# Lab2-th.net
KiCad netlist of a schematic drawn in EAGLE
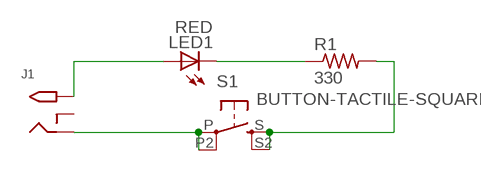
[diagram p0: schematic, sheet 1]

(export (version "E")
  (design (tool "Eeschema 10.0.6"))
  (components
    (comp (ref "J1")
      (value "2.1MMJACKTHM")
      (footprint "eagle-import:PJ-102A")
      (libsource (lib "eagle-import") (part "2.1MMJACKTHM"))
    )
    (comp (ref "LED1")
      (value "RED")
      (footprint "eagle-import:LED5MM")
      (libsource (lib "eagle-import") (part "LED5MM"))
    )
    (comp (ref "R1")
      (value "330")
      (footprint "eagle-import:RESAD1160W55L680D260_HS")
      (libsource (lib "eagle-import") (part "RESISTORTH-1/4W-CARBON"))
    )
    (comp (ref "S1")
      (value "BUTTON-TACTILE-SQUARE")
      (footprint "eagle-import:BUTTON-TACTILE-SQUARE-ADAFRUIT1010")
      (libsource (lib "eagle-import") (part "BUTTON-TACTILE-SQUARE"))
    )
  )
  (nets
    (net (code "1") (name "Net-(J1-PadTIP)") (class "Default")
      (node (ref "J1") (pin "TIP") (pinfunction "TIP_TIP") (pintype "bidirectional"))
      (node (ref "LED1") (pin "A") (pinfunction "A_A") (pintype "passive"))
    )
    (net (code "2") (name "Net-(LED1-C)") (class "Default")
      (node (ref "LED1") (pin "K") (pinfunction "C_K") (pintype "passive"))
      (node (ref "R1") (pin "1") (pinfunction "1_1") (pintype "passive"))
    )
    (net (code "3") (name "Net-(S1-P1)") (class "Default")
      (node (ref "J1") (pin "RING") (pinfunction "RING_RING") (pintype "bidirectional"))
      (node (ref "S1") (pin "P") (pinfunction "P_P") (pintype "passive"))
      (node (ref "S1") (pin "P2") (pinfunction "P1_P2") (pintype "passive"))
    )
    (net (code "4") (name "Net-(S1-S1)") (class "Default")
      (node (ref "R1") (pin "2") (pinfunction "2_2") (pintype "passive"))
      (node (ref "S1") (pin "S") (pinfunction "S_S") (pintype "passive"))
      (node (ref "S1") (pin "S2") (pinfunction "S1_S2") (pintype "passive"))
    )
    (net (code "5") (name "unconnected-(J1-PadRING_SW)") (class "Default")
      (node (ref "J1") (pin "RING_SW") (pinfunction "RING_SW_RING_SW") (pintype "bidirectional"))
    )
  )
)
